# IO_ctrl.net
KiCad netlist of a schematic drawn in Altium Designer
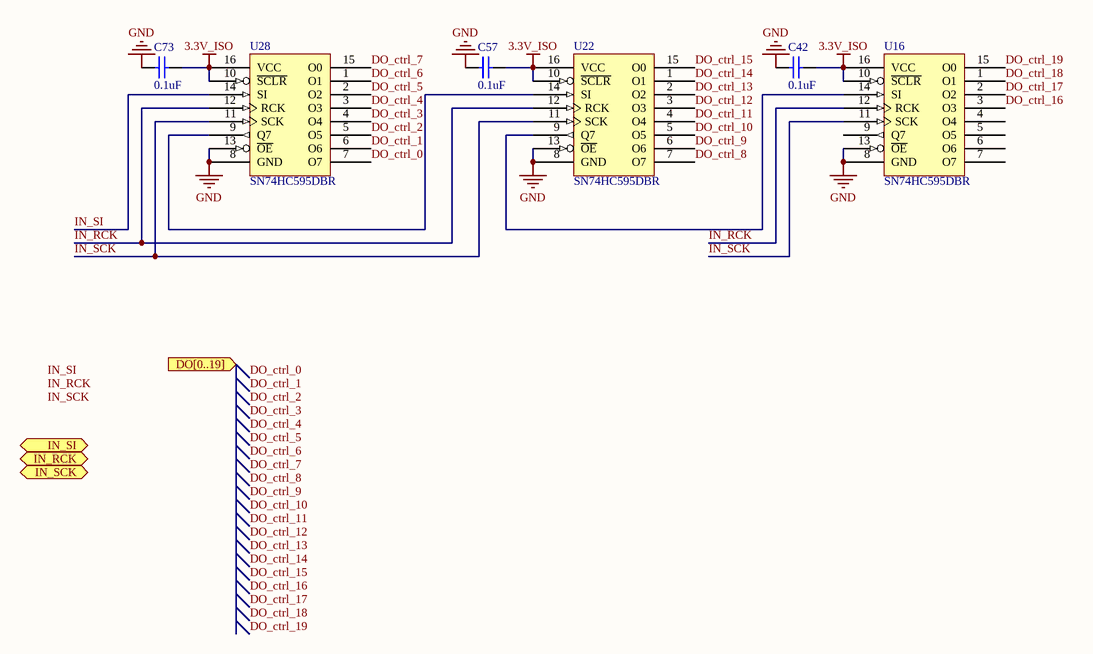
[diagram p0: IO_ctrl.SchDoc]

(export (version "E")
  (design (tool "Eeschema 10.0.6"))
  (components
    (comp (ref "C42")
      (value "0.1uF")
      (footprint "0603C")
      (description "Capacitor")
      (fields (field (name "PUBLISHER") "Altium Limited"))
      (libsource (lib "Miscellaneous Devices") (part "Cap"))
    )
    (comp (ref "C57")
      (value "0.1uF")
      (footprint "0603C")
      (description "Capacitor")
      (fields (field (name "PUBLISHER") "Altium Limited"))
      (libsource (lib "Miscellaneous Devices") (part "Cap"))
    )
    (comp (ref "C73")
      (value "0.1uF")
      (footprint "0603C")
      (description "Capacitor")
      (fields (field (name "PUBLISHER") "Altium Limited"))
      (libsource (lib "Miscellaneous Devices") (part "Cap"))
    )
    (comp (ref "U16") (value "SN74HC595DBR") (footprint "SSOP16") (libsource (lib "DI16") (part "74HC595")))
    (comp (ref "U22") (value "SN74HC595DBR") (footprint "SSOP16") (libsource (lib "DI16") (part "74HC595")))
    (comp (ref "U28") (value "SN74HC595DBR") (footprint "SSOP16") (libsource (lib "DI16") (part "74HC595")))
  )
  (nets
    (net (code "22") (name "/DO_ctrl_0") (class "Default")
      (node (ref "U28") (pin "7") (pinfunction "O7_7") (pintype "tri_state"))
    )
    (net (code "23") (name "/DO_ctrl_1") (class "Default")
      (node (ref "U28") (pin "6") (pinfunction "O6_6") (pintype "tri_state"))
    )
    (net (code "24") (name "/DO_ctrl_2") (class "Default")
      (node (ref "U28") (pin "5") (pinfunction "O5_5") (pintype "tri_state"))
    )
    (net (code "25") (name "/DO_ctrl_3") (class "Default")
      (node (ref "U28") (pin "4") (pinfunction "O4_4") (pintype "tri_state"))
    )
    (net (code "26") (name "/DO_ctrl_4") (class "Default")
      (node (ref "U28") (pin "3") (pinfunction "O3_3") (pintype "tri_state"))
    )
    (net (code "27") (name "/DO_ctrl_5") (class "Default")
      (node (ref "U28") (pin "2") (pinfunction "O2_2") (pintype "tri_state"))
    )
    (net (code "28") (name "/DO_ctrl_6") (class "Default")
      (node (ref "U28") (pin "1") (pinfunction "O1_1") (pintype "tri_state"))
    )
    (net (code "29") (name "/DO_ctrl_7") (class "Default")
      (node (ref "U28") (pin "15") (pinfunction "O0_15") (pintype "tri_state"))
    )
    (net (code "30") (name "/DO_ctrl_8") (class "Default")
      (node (ref "U22") (pin "7") (pinfunction "O7_7") (pintype "tri_state"))
    )
    (net (code "31") (name "/DO_ctrl_9") (class "Default")
      (node (ref "U22") (pin "6") (pinfunction "O6_6") (pintype "tri_state"))
    )
    (net (code "32") (name "/DO_ctrl_10") (class "Default")
      (node (ref "U22") (pin "5") (pinfunction "O5_5") (pintype "tri_state"))
    )
    (net (code "33") (name "/DO_ctrl_11") (class "Default")
      (node (ref "U22") (pin "4") (pinfunction "O4_4") (pintype "tri_state"))
    )
    (net (code "34") (name "/DO_ctrl_12") (class "Default")
      (node (ref "U22") (pin "3") (pinfunction "O3_3") (pintype "tri_state"))
    )
    (net (code "35") (name "/DO_ctrl_13") (class "Default")
      (node (ref "U22") (pin "2") (pinfunction "O2_2") (pintype "tri_state"))
    )
    (net (code "36") (name "/DO_ctrl_14") (class "Default")
      (node (ref "U22") (pin "1") (pinfunction "O1_1") (pintype "tri_state"))
    )
    (net (code "37") (name "/DO_ctrl_15") (class "Default")
      (node (ref "U22") (pin "15") (pinfunction "O0_15") (pintype "tri_state"))
    )
    (net (code "38") (name "/DO_ctrl_16") (class "Default")
      (node (ref "U16") (pin "3") (pinfunction "O3_3") (pintype "tri_state"))
    )
    (net (code "39") (name "/DO_ctrl_17") (class "Default")
      (node (ref "U16") (pin "2") (pinfunction "O2_2") (pintype "tri_state"))
    )
    (net (code "40") (name "/DO_ctrl_18") (class "Default")
      (node (ref "U16") (pin "1") (pinfunction "O1_1") (pintype "tri_state"))
    )
    (net (code "41") (name "/DO_ctrl_19") (class "Default")
      (node (ref "U16") (pin "15") (pinfunction "O0_15") (pintype "tri_state"))
    )
    (net (code "42") (name "/IN_RCK") (class "Default")
      (node (ref "U16") (pin "12") (pinfunction "RCK_12") (pintype "input"))
      (node (ref "U22") (pin "12") (pinfunction "RCK_12") (pintype "input"))
      (node (ref "U28") (pin "12") (pinfunction "RCK_12") (pintype "input"))
    )
    (net (code "43") (name "/IN_SCK") (class "Default")
      (node (ref "U16") (pin "11") (pinfunction "SCK_11") (pintype "input"))
      (node (ref "U22") (pin "11") (pinfunction "SCK_11") (pintype "input"))
      (node (ref "U28") (pin "11") (pinfunction "SCK_11") (pintype "input"))
    )
    (net (code "44") (name "/IN_SI") (class "Default")
      (node (ref "U28") (pin "14") (pinfunction "SI_14") (pintype "input"))
    )
    (net (code "45") (name "3.3V_ISO") (class "Default")
      (node (ref "C42") (pin "1") (pinfunction "1_1") (pintype "passive"))
      (node (ref "C57") (pin "1") (pinfunction "1_1") (pintype "passive"))
      (node (ref "C73") (pin "1") (pinfunction "1_1") (pintype "passive"))
      (node (ref "U16") (pin "10") (pinfunction "~{SCLR}_10") (pintype "input"))
      (node (ref "U16") (pin "16") (pinfunction "VCC_16") (pintype "power_in"))
      (node (ref "U22") (pin "10") (pinfunction "~{SCLR}_10") (pintype "input"))
      (node (ref "U22") (pin "16") (pinfunction "VCC_16") (pintype "power_in"))
      (node (ref "U28") (pin "10") (pinfunction "~{SCLR}_10") (pintype "input"))
      (node (ref "U28") (pin "16") (pinfunction "VCC_16") (pintype "power_in"))
    )
    (net (code "46") (name "GND") (class "Default")
      (node (ref "C42") (pin "2") (pinfunction "2_2") (pintype "passive"))
      (node (ref "C57") (pin "2") (pinfunction "2_2") (pintype "passive"))
      (node (ref "C73") (pin "2") (pinfunction "2_2") (pintype "passive"))
      (node (ref "U16") (pin "13") (pinfunction "~{OE}_13") (pintype "input"))
      (node (ref "U16") (pin "8") (pinfunction "GND_8") (pintype "power_in"))
      (node (ref "U22") (pin "13") (pinfunction "~{OE}_13") (pintype "input"))
      (node (ref "U22") (pin "8") (pinfunction "GND_8") (pintype "power_in"))
      (node (ref "U28") (pin "13") (pinfunction "~{OE}_13") (pintype "input"))
      (node (ref "U28") (pin "8") (pinfunction "GND_8") (pintype "power_in"))
    )
    (net (code "47") (name "Net-(U16-SI)") (class "Default")
      (node (ref "U16") (pin "14") (pinfunction "SI_14") (pintype "input"))
      (node (ref "U22") (pin "9") (pinfunction "Q7_9") (pintype "output"))
    )
    (net (code "48") (name "Net-(U22-SI)") (class "Default")
      (node (ref "U22") (pin "14") (pinfunction "SI_14") (pintype "input"))
      (node (ref "U28") (pin "9") (pinfunction "Q7_9") (pintype "output"))
    )
    (net (code "49") (name "unconnected-(U16-O4-Pad4)") (class "Default")
      (node (ref "U16") (pin "4") (pinfunction "O4_4") (pintype "tri_state"))
    )
    (net (code "50") (name "unconnected-(U16-O5-Pad5)") (class "Default")
      (node (ref "U16") (pin "5") (pinfunction "O5_5") (pintype "tri_state"))
    )
    (net (code "51") (name "unconnected-(U16-O6-Pad6)") (class "Default")
      (node (ref "U16") (pin "6") (pinfunction "O6_6") (pintype "tri_state"))
    )
    (net (code "52") (name "unconnected-(U16-O7-Pad7)") (class "Default")
      (node (ref "U16") (pin "7") (pinfunction "O7_7") (pintype "tri_state"))
    )
    (net (code "53") (name "unconnected-(U16-Q7-Pad9)") (class "Default")
      (node (ref "U16") (pin "9") (pinfunction "Q7_9") (pintype "output"))
    )
  )
)
